# CH554-dev-board.net
KiCad netlist of a schematic drawn in EAGLE
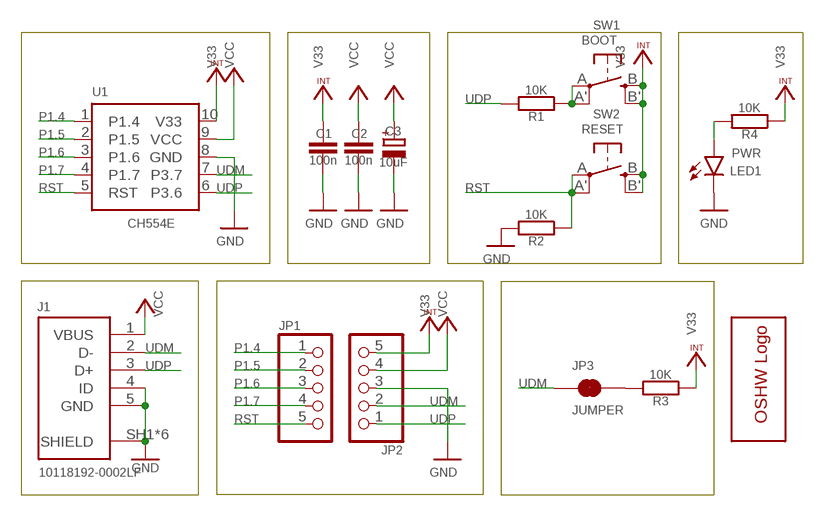
[diagram p0: schematic, sheet 1]

(export (version "E")
  (design (tool "Eeschema 10.0.6"))
  (components
    (comp (ref "C1")
      (value "100n")
      (footprint "eagle-import:C0603")
      (libsource (lib "eagle-import") (part "C-EUC0603"))
    )
    (comp (ref "C2")
      (value "100n")
      (footprint "eagle-import:C0603")
      (libsource (lib "eagle-import") (part "C-EUC0603"))
    )
    (comp (ref "C3")
      (value "10uF")
      (footprint "eagle-import:A_3216-18R")
      (libsource (lib "eagle-import") (part "CPOL-EUA/3216-18R"))
    )
    (comp (ref "GOLD_ORB_SM1")
      (value "OSHWLOGOLOGO5MM")
      (footprint "eagle-import:OSHW_5MM")
      (libsource (lib "eagle-import") (part "OSHWLOGOLOGO5MM"))
    )
    (comp (ref "J1")
      (value "10118192-0002LF")
      (footprint "eagle-import:10118192-0002LF")
      (fields
        (field (name "DIGIKEY_PARTNO") "609-5379-2-ND")
        (field (name "MANUFACTURER") "Amphenol ICC (FCI)")
        (field (name "CREATED_BY") "PCBLayout.com")
      )
      (libsource (lib "eagle-import") (part "10118192-0002LF"))
    )
    (comp (ref "JP1")
      (value "PINHD-1X5")
      (footprint "eagle-import:1X05")
      (libsource (lib "eagle-import") (part "PINHD-1X5"))
    )
    (comp (ref "JP2")
      (value "PINHD-1X5")
      (footprint "eagle-import:1X05")
      (libsource (lib "eagle-import") (part "PINHD-1X5"))
    )
    (comp (ref "JP3")
      (value "JUMPER")
      (footprint "eagle-import:SMT-JUMPER_2_NC_TRACE_NO-SILK")
      (libsource (lib "eagle-import") (part "JUMPER-SMT_2_NC_TRACE_NO-SILK"))
    )
    (comp (ref "LED1")
      (value "PWR")
      (footprint "eagle-import:CHIP-LED0603")
      (libsource (lib "eagle-import") (part "LEDCHIP-LED0603"))
    )
    (comp (ref "R1")
      (value "10K")
      (footprint "eagle-import:R0603")
      (libsource (lib "eagle-import") (part "R-EU_R0603"))
    )
    (comp (ref "R2")
      (value "10K")
      (footprint "eagle-import:R0603")
      (libsource (lib "eagle-import") (part "R-EU_R0603"))
    )
    (comp (ref "R3")
      (value "10K")
      (footprint "eagle-import:R0603")
      (libsource (lib "eagle-import") (part "R-EU_R0603"))
    )
    (comp (ref "R4")
      (value "10K")
      (footprint "eagle-import:R0603")
      (libsource (lib "eagle-import") (part "R-EU_R0603"))
    )
    (comp (ref "SW1")
      (value "BOOT")
      (footprint "eagle-import:EVQ-Q2")
      (libsource (lib "eagle-import") (part "SPST_TACT-EVQQ2"))
    )
    (comp (ref "SW2")
      (value "RESET")
      (footprint "eagle-import:EVQ-Q2")
      (libsource (lib "eagle-import") (part "SPST_TACT-EVQQ2"))
    )
    (comp (ref "U1")
      (value "CH554E")
      (footprint "eagle-import:MSOP10")
      (libsource (lib "eagle-import") (part "CH554E"))
    )
  )
  (nets
    (net (code "1") (name "/P1.4") (class "Default")
      (node (ref "JP1") (pin "1") (pinfunction "1_1") (pintype "passive"))
      (node (ref "U1") (pin "1") (pinfunction "P1.4_1") (pintype "bidirectional"))
    )
    (net (code "2") (name "/P1.5") (class "Default")
      (node (ref "JP1") (pin "2") (pinfunction "2_2") (pintype "passive"))
      (node (ref "U1") (pin "2") (pinfunction "P1.5_2") (pintype "bidirectional"))
    )
    (net (code "3") (name "/P1.6") (class "Default")
      (node (ref "JP1") (pin "3") (pinfunction "3_3") (pintype "passive"))
      (node (ref "U1") (pin "3") (pinfunction "P1.6_3") (pintype "bidirectional"))
    )
    (net (code "4") (name "/P1.7") (class "Default")
      (node (ref "JP1") (pin "4") (pinfunction "4_4") (pintype "passive"))
      (node (ref "U1") (pin "4") (pinfunction "P1.7_4") (pintype "bidirectional"))
    )
    (net (code "5") (name "/RST") (class "Default")
      (node (ref "JP1") (pin "5") (pinfunction "5_5") (pintype "passive"))
      (node (ref "R2") (pin "1") (pinfunction "1_1") (pintype "passive"))
      (node (ref "SW2") (pin "A") (pinfunction "P_A") (pintype "passive"))
      (node (ref "SW2") (pin "A'") (pinfunction "P1_A'") (pintype "passive"))
      (node (ref "U1") (pin "5") (pinfunction "RST_5") (pintype "input"))
    )
    (net (code "6") (name "/UDM") (class "Default")
      (node (ref "J1") (pin "2") (pinfunction "D-_2") (pintype "passive"))
      (node (ref "JP2") (pin "2") (pinfunction "2_2") (pintype "passive"))
      (node (ref "JP3") (pin "1") (pinfunction "1_1") (pintype "passive"))
      (node (ref "U1") (pin "7") (pinfunction "P3.7_7") (pintype "bidirectional"))
    )
    (net (code "7") (name "/UDP") (class "Default")
      (node (ref "J1") (pin "3") (pinfunction "D+_3") (pintype "passive"))
      (node (ref "JP2") (pin "1") (pinfunction "1_1") (pintype "passive"))
      (node (ref "R1") (pin "2") (pinfunction "2_2") (pintype "passive"))
      (node (ref "U1") (pin "6") (pinfunction "P3.6_6") (pintype "bidirectional"))
    )
    (net (code "8") (name "GND") (class "Default")
      (node (ref "C1") (pin "2") (pinfunction "2_2") (pintype "passive"))
      (node (ref "C2") (pin "2") (pinfunction "2_2") (pintype "passive"))
      (node (ref "C3") (pin "-") (pinfunction "-_-") (pintype "passive"))
      (node (ref "J1") (pin "4") (pinfunction "ID_4") (pintype "passive"))
      (node (ref "J1") (pin "5") (pinfunction "GND_5") (pintype "passive"))
      (node (ref "J1") (pin "SH1") (pinfunction "SHIELD_SH1") (pintype "power_in"))
      (node (ref "J1") (pin "SH2") (pinfunction "SHIELD_SH2") (pintype "power_in"))
      (node (ref "J1") (pin "SH3") (pinfunction "SHIELD_SH3") (pintype "power_in"))
      (node (ref "J1") (pin "SH4") (pinfunction "SHIELD_SH4") (pintype "power_in"))
      (node (ref "J1") (pin "SH5") (pinfunction "SHIELD_SH5") (pintype "power_in"))
      (node (ref "J1") (pin "SH6") (pinfunction "SHIELD_SH6") (pintype "power_in"))
      (node (ref "JP2") (pin "3") (pinfunction "3_3") (pintype "passive"))
      (node (ref "LED1") (pin "C") (pinfunction "C_C") (pintype "passive"))
      (node (ref "R2") (pin "2") (pinfunction "2_2") (pintype "passive"))
      (node (ref "U1") (pin "8") (pinfunction "GND_8") (pintype "power_in"))
    )
    (net (code "9") (name "Net-(JP3-Pad2)") (class "Default")
      (node (ref "JP3") (pin "2") (pinfunction "2_2") (pintype "passive"))
      (node (ref "R3") (pin "2") (pinfunction "2_2") (pintype "passive"))
    )
    (net (code "10") (name "Net-(LED1-PadA)") (class "Default")
      (node (ref "LED1") (pin "A") (pinfunction "A_A") (pintype "passive"))
      (node (ref "R4") (pin "2") (pinfunction "2_2") (pintype "passive"))
    )
    (net (code "11") (name "Net-(SW1-P)") (class "Default")
      (node (ref "R1") (pin "1") (pinfunction "1_1") (pintype "passive"))
      (node (ref "SW1") (pin "A") (pinfunction "P_A") (pintype "passive"))
      (node (ref "SW1") (pin "A'") (pinfunction "P1_A'") (pintype "passive"))
    )
    (net (code "12") (name "V33") (class "Default")
      (node (ref "C1") (pin "1") (pinfunction "1_1") (pintype "passive"))
      (node (ref "JP2") (pin "5") (pinfunction "5_5") (pintype "passive"))
      (node (ref "R3") (pin "1") (pinfunction "1_1") (pintype "passive"))
      (node (ref "R4") (pin "1") (pinfunction "1_1") (pintype "passive"))
      (node (ref "SW1") (pin "B") (pinfunction "S_B") (pintype "passive"))
      (node (ref "SW1") (pin "B'") (pinfunction "S1_B'") (pintype "passive"))
      (node (ref "SW2") (pin "B") (pinfunction "S_B") (pintype "passive"))
      (node (ref "SW2") (pin "B'") (pinfunction "S1_B'") (pintype "passive"))
      (node (ref "U1") (pin "10") (pinfunction "V33_10") (pintype "power_in"))
    )
    (net (code "13") (name "VCC") (class "Default")
      (node (ref "C2") (pin "1") (pinfunction "1_1") (pintype "passive"))
      (node (ref "C3") (pin "+") (pinfunction "+_+") (pintype "passive"))
      (node (ref "J1") (pin "1") (pinfunction "VBUS_1") (pintype "passive"))
      (node (ref "JP2") (pin "4") (pinfunction "4_4") (pintype "passive"))
      (node (ref "U1") (pin "9") (pinfunction "VCC_9") (pintype "power_in"))
    )
  )
)
